# RS485_tranceiver.net
KiCad netlist of a schematic drawn in Altium Designer
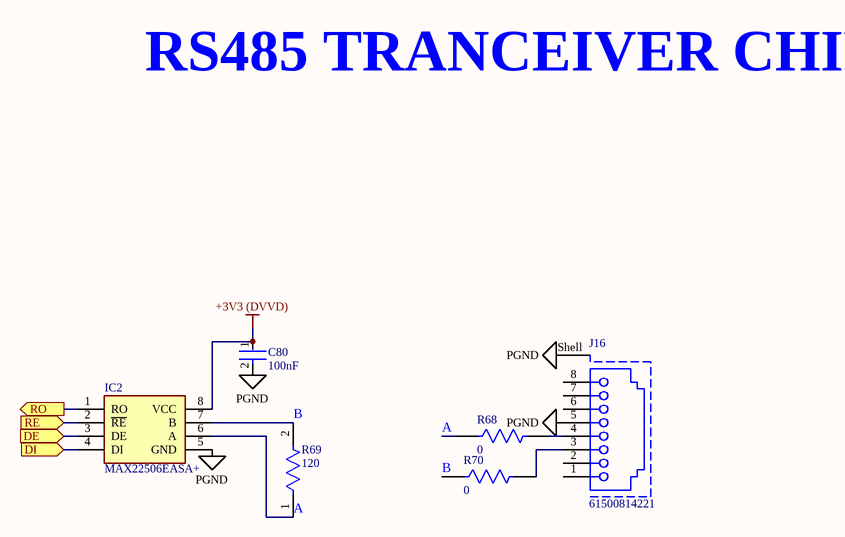
[diagram p0: RS485_tranceiver.SchDoc]

(export (version "E")
  (design (tool "Eeschema 10.0.6"))
  (components
    (comp (ref "C80")
      (value "100nF")
      (footprint "FP-GRM15-MFG")
      (description "CAP CER 0.1UF 16V X7R 0402")
      (fields (field (name "MANUFACTURER PART NUMBER") "GRM155R71C104KA88D") (field (name "TOLERANCE") "10%"))
      (libsource (lib "Altium Content Vault") (part "236180d848d6139a670b325ea6854c9"))
    )
    (comp (ref "IC2")
      (value "MAX22506EASA+")
      (footprint "SamacSys:SOIC127P600X175-8N")
      (description "Integrated Circuit")
      (fields (field (name "MOUSER PART NUMBER") "700-MAX22506EASA+"))
      (libsource (lib "*") (part "MAX22506EASA+"))
    )
    (comp (ref "J16")
      (value "61500814221")
      (footprint "61500814221")
      (libsource (lib "Altium Content Vault") (part "8P8C - 1 Port - Shielded"))
    )
    (comp (ref "R68")
      (value "0")
      (footprint "FP-CRCW1206-MFG")
      (description "CRCW12060000ZSTA Zero Ohm Resistor, Jumper, 1206 [3216 Metric], Thick Film, 250 mW, Surface Mount")
      (libsource (lib "") (part "1029c3af85768c4190bb7ad29bc67b5_1"))
    )
    (comp (ref "R69")
      (value "120")
      (footprint "FP-CRCW1206-MFG")
      (description "CRCW12060000ZS120 Ohm Resistor, Jumper, 1206 [3216 Metric], Thick Film, 250 mW, Surface Mount")
      (libsource (lib "Altium Content Vault") (part "1029c3af85768c4190bb7ad29bc67b5"))
    )
    (comp (ref "R70")
      (value "0")
      (footprint "FP-CRCW1206-MFG")
      (description "CRCW12060000ZSTA Zero Ohm Resistor, Jumper, 1206 [3216 Metric], Thick Film, 250 mW, Surface Mount")
      (libsource (lib "") (part "1029c3af85768c4190bb7ad29bc67b5_1"))
    )
  )
  (nets
    (net (code "1") (name "+3V3 (DVVD)") (class "Default")
      (node (ref "C80") (pin "1") (pinfunction "1_1") (pintype "passive"))
      (node (ref "IC2") (pin "8") (pinfunction "VCC_8") (pintype "passive"))
    )
    (net (code "2") (name "/A") (class "Default")
      (node (ref "IC2") (pin "6") (pinfunction "A_6") (pintype "passive"))
      (node (ref "R68") (pin "1") (pinfunction "1_1") (pintype "passive"))
      (node (ref "R69") (pin "1") (pinfunction "1_1") (pintype "passive"))
    )
    (net (code "3") (name "/B") (class "Default")
      (node (ref "IC2") (pin "7") (pinfunction "B_7") (pintype "passive"))
      (node (ref "R69") (pin "2") (pinfunction "2_2") (pintype "passive"))
      (node (ref "R70") (pin "1") (pinfunction "1_1") (pintype "passive"))
    )
    (net (code "4") (name "/DE") (class "Default")
      (node (ref "IC2") (pin "3") (pinfunction "DE_3") (pintype "passive"))
    )
    (net (code "5") (name "/DI") (class "Default")
      (node (ref "IC2") (pin "4") (pinfunction "DI_4") (pintype "passive"))
    )
    (net (code "6") (name "/RE") (class "Default")
      (node (ref "IC2") (pin "2") (pinfunction "~{RE}_2") (pintype "passive"))
    )
    (net (code "7") (name "/RO") (class "Default")
      (node (ref "IC2") (pin "1") (pinfunction "RO_1") (pintype "passive"))
    )
    (net (code "8") (name "Net-(J16-Pad3)") (class "Default")
      (node (ref "J16") (pin "3") (pinfunction "3_3") (pintype "passive"))
      (node (ref "R70") (pin "2") (pinfunction "2_2") (pintype "passive"))
    )
    (net (code "9") (name "Net-(J16-Pad4)") (class "Default")
      (node (ref "J16") (pin "4") (pinfunction "4_4") (pintype "passive"))
      (node (ref "R68") (pin "2") (pinfunction "2_2") (pintype "passive"))
    )
    (net (code "10") (name "PGND") (class "Default")
      (node (ref "C80") (pin "2") (pinfunction "2_2") (pintype "passive"))
      (node (ref "IC2") (pin "5") (pinfunction "GND_5") (pintype "passive"))
      (node (ref "J16") (pin "5") (pinfunction "5_5") (pintype "passive"))
      (node (ref "J16") (pin "Shell") (pinfunction "Shell_Shell") (pintype "passive"))
    )
    (net (code "11") (name "unconnected-(J16-Pad1)") (class "Default")
      (node (ref "J16") (pin "1") (pinfunction "1_1") (pintype "passive"))
    )
    (net (code "12") (name "unconnected-(J16-Pad2)") (class "Default")
      (node (ref "J16") (pin "2") (pinfunction "2_2") (pintype "passive"))
    )
    (net (code "13") (name "unconnected-(J16-Pad6)") (class "Default")
      (node (ref "J16") (pin "6") (pinfunction "6_6") (pintype "passive"))
    )
    (net (code "14") (name "unconnected-(J16-Pad7)") (class "Default")
      (node (ref "J16") (pin "7") (pinfunction "7_7") (pintype "passive"))
    )
    (net (code "15") (name "unconnected-(J16-Pad8)") (class "Default")
      (node (ref "J16") (pin "8") (pinfunction "8_8") (pintype "passive"))
    )
  )
)
